# SHDN-IMD-S02-V00-IMDConnection.net
KiCad netlist of a schematic drawn in Altium Designer
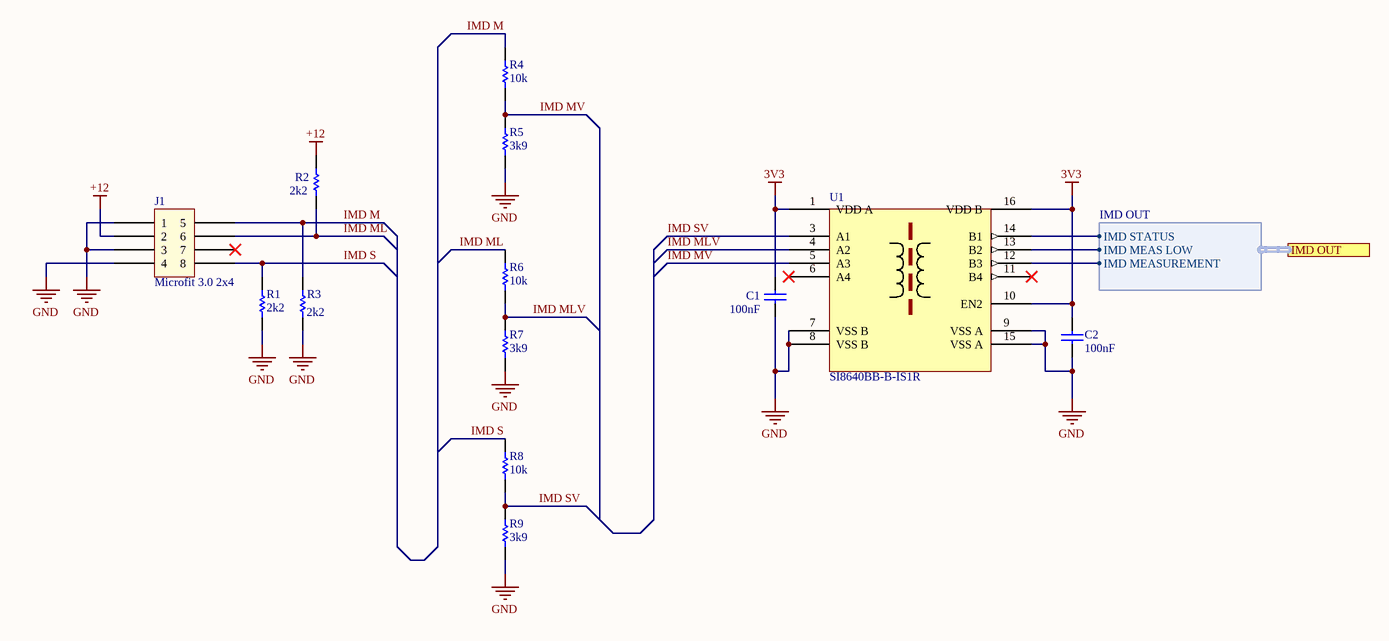
[diagram p0: SHDN-IMD-S02-V00-IMDConnection.SchDoc]

(export (version "E")
  (design (tool "Eeschema 10.0.6"))
  (components
    (comp (ref "C1")
      (value "100nF")
      (footprint "Cap_Ceramic_0603")
      (description "Capacitor, Ceramic, SMD, 100nF, 50V, 5%, X7R, 0603")
      (libsource (lib "StandardCapacitors") (part "100nF 50V 5% X7R 0603"))
    )
    (comp (ref "C2")
      (value "100nF")
      (footprint "Cap_Ceramic_0603")
      (description "Capacitor, Ceramic, SMD, 100nF, 50V, 5%, X7R, 0603")
      (libsource (lib "StandardCapacitors") (part "100nF 50V 5% X7R 0603"))
    )
    (comp (ref "J1")
      (value "Microfit 3.0 2x4")
      (footprint "Microfit_2X4_R_TH")
      (libsource (lib "QUTMS_MicrofitLibrary") (part "Microfit_2x4"))
    )
    (comp (ref "R1")
      (value "2k2")
      (footprint "Res_ThinFilm_0603")
      (description "Resistor, SMD, 2k2, 0.1W, 5%, 0603")
      (libsource (lib "StandardResistors") (part "2k2 5% 0603"))
    )
    (comp (ref "R2")
      (value "2k2")
      (footprint "Res_ThinFilm_0603")
      (description "Resistor, SMD, 2k2, 0.1W, 5%, 0603")
      (libsource (lib "StandardResistors") (part "2k2 5% 0603"))
    )
    (comp (ref "R3")
      (value "2k2")
      (footprint "Res_ThinFilm_0603")
      (description "Resistor, SMD, 2k2, 0.1W, 5%, 0603")
      (libsource (lib "StandardResistors") (part "2k2 5% 0603"))
    )
    (comp (ref "R4")
      (value "10k")
      (footprint "Res_ThinFilm_0603")
      (description "Resistor, SMD, 10k, 0.1W, 1%, 0603")
      (libsource (lib "StandardResistors") (part "10k 1% 0603"))
    )
    (comp (ref "R5")
      (value "3k9")
      (footprint "Res_ThinFilm_0603")
      (description "Resistor, SMD, 3k9, 0.1W, 5%, 0603")
      (libsource (lib "StandardResistors") (part "3k9 5% 0603"))
    )
    (comp (ref "R6")
      (value "10k")
      (footprint "Res_ThinFilm_0603")
      (description "Resistor, SMD, 10k, 0.1W, 1%, 0603")
      (libsource (lib "StandardResistors") (part "10k 1% 0603"))
    )
    (comp (ref "R7")
      (value "3k9")
      (footprint "Res_ThinFilm_0603")
      (description "Resistor, SMD, 3k9, 0.1W, 5%, 0603")
      (libsource (lib "StandardResistors") (part "3k9 5% 0603"))
    )
    (comp (ref "R8")
      (value "10k")
      (footprint "Res_ThinFilm_0603")
      (description "Resistor, SMD, 10k, 0.1W, 1%, 0603")
      (libsource (lib "StandardResistors") (part "10k 1% 0603"))
    )
    (comp (ref "R9")
      (value "3k9")
      (footprint "Res_ThinFilm_0603")
      (description "Resistor, SMD, 3k9, 0.1W, 5%, 0603")
      (libsource (lib "StandardResistors") (part "3k9 5% 0603"))
    )
    (comp (ref "U1")
      (value "SI8640BB-B-IS1R")
      (footprint "SI8640BB-B-IS1R")
      (libsource (lib "QUTMS_IsolatorLibrary") (part "SI8640BB-B-IS1R"))
    )
  )
  (nets
    (net (code "3") (name "+12") (class "Default")
      (node (ref "J1") (pin "2") (pinfunction "2_2") (pintype "passive"))
      (node (ref "R2") (pin "2") (pinfunction "2_2") (pintype "passive"))
    )
    (net (code "4") (name "/IMD M") (class "Default")
      (node (ref "J1") (pin "5") (pinfunction "5_5") (pintype "passive"))
      (node (ref "R3") (pin "2") (pinfunction "2_2") (pintype "passive"))
      (node (ref "R4") (pin "2") (pinfunction "2_2") (pintype "passive"))
    )
    (net (code "5") (name "/IMD MEAS LOW") (class "Default")
      (node (ref "U1") (pin "13") (pinfunction "B2_13") (pintype "output"))
    )
    (net (code "6") (name "/IMD MEASUREMENT") (class "Default")
      (node (ref "U1") (pin "12") (pinfunction "B3_12") (pintype "output"))
    )
    (net (code "7") (name "/IMD ML") (class "Default")
      (node (ref "J1") (pin "6") (pinfunction "6_6") (pintype "passive"))
      (node (ref "R2") (pin "1") (pinfunction "1_1") (pintype "passive"))
      (node (ref "R6") (pin "2") (pinfunction "2_2") (pintype "passive"))
    )
    (net (code "8") (name "/IMD MLV") (class "Default")
      (node (ref "R6") (pin "1") (pinfunction "1_1") (pintype "passive"))
      (node (ref "R7") (pin "2") (pinfunction "2_2") (pintype "passive"))
      (node (ref "U1") (pin "4") (pinfunction "A2_4") (pintype "passive"))
    )
    (net (code "9") (name "/IMD MV") (class "Default")
      (node (ref "R4") (pin "1") (pinfunction "1_1") (pintype "passive"))
      (node (ref "R5") (pin "2") (pinfunction "2_2") (pintype "passive"))
      (node (ref "U1") (pin "5") (pinfunction "A3_5") (pintype "passive"))
    )
    (net (code "10") (name "/IMD S") (class "Default")
      (node (ref "J1") (pin "8") (pinfunction "8_8") (pintype "passive"))
      (node (ref "R1") (pin "2") (pinfunction "2_2") (pintype "passive"))
      (node (ref "R8") (pin "2") (pinfunction "2_2") (pintype "passive"))
    )
    (net (code "11") (name "/IMD STATUS") (class "Default")
      (node (ref "U1") (pin "14") (pinfunction "B1_14") (pintype "output"))
    )
    (net (code "12") (name "/IMD SV") (class "Default")
      (node (ref "R8") (pin "1") (pinfunction "1_1") (pintype "passive"))
      (node (ref "R9") (pin "2") (pinfunction "2_2") (pintype "passive"))
      (node (ref "U1") (pin "3") (pinfunction "A1_3") (pintype "passive"))
    )
    (net (code "14") (name "3V3") (class "Default")
      (node (ref "C1") (pin "2") (pinfunction "2_2") (pintype "passive"))
      (node (ref "C2") (pin "2") (pinfunction "2_2") (pintype "passive"))
      (node (ref "U1") (pin "1") (pinfunction "VDD_A_1") (pintype "passive"))
      (node (ref "U1") (pin "10") (pinfunction "EN2_10") (pintype "passive"))
      (node (ref "U1") (pin "16") (pinfunction "VDD_B_16") (pintype "passive"))
    )
    (net (code "15") (name "GND") (class "Default")
      (node (ref "C1") (pin "1") (pinfunction "1_1") (pintype "passive"))
      (node (ref "C2") (pin "1") (pinfunction "1_1") (pintype "passive"))
      (node (ref "J1") (pin "1") (pinfunction "1_1") (pintype "passive"))
      (node (ref "J1") (pin "3") (pinfunction "3_3") (pintype "passive"))
      (node (ref "J1") (pin "4") (pinfunction "4_4") (pintype "passive"))
      (node (ref "R1") (pin "1") (pinfunction "1_1") (pintype "passive"))
      (node (ref "R3") (pin "1") (pinfunction "1_1") (pintype "passive"))
      (node (ref "R5") (pin "1") (pinfunction "1_1") (pintype "passive"))
      (node (ref "R7") (pin "1") (pinfunction "1_1") (pintype "passive"))
      (node (ref "R9") (pin "1") (pinfunction "1_1") (pintype "passive"))
      (node (ref "U1") (pin "15") (pinfunction "VSS_A_15") (pintype "passive"))
      (node (ref "U1") (pin "7") (pinfunction "VSS_B_7") (pintype "passive"))
      (node (ref "U1") (pin "8") (pinfunction "VSS_B_8") (pintype "passive"))
      (node (ref "U1") (pin "9") (pinfunction "VSS_A_9") (pintype "passive"))
    )
    (net (code "16") (name "unconnected-(J1-Pad7)") (class "Default")
      (node (ref "J1") (pin "7") (pinfunction "7_7") (pintype "passive+no_connect"))
    )
    (net (code "17") (name "unconnected-(U1-A4-Pad6)") (class "Default")
      (node (ref "U1") (pin "6") (pinfunction "A4_6") (pintype "passive+no_connect"))
    )
    (net (code "18") (name "unconnected-(U1-B4-Pad11)") (class "Default")
      (node (ref "U1") (pin "11") (pinfunction "B4_11") (pintype "output+no_connect"))
    )
  )
)
